# IO_RF.net
KiCad netlist of a schematic drawn in Altium Designer
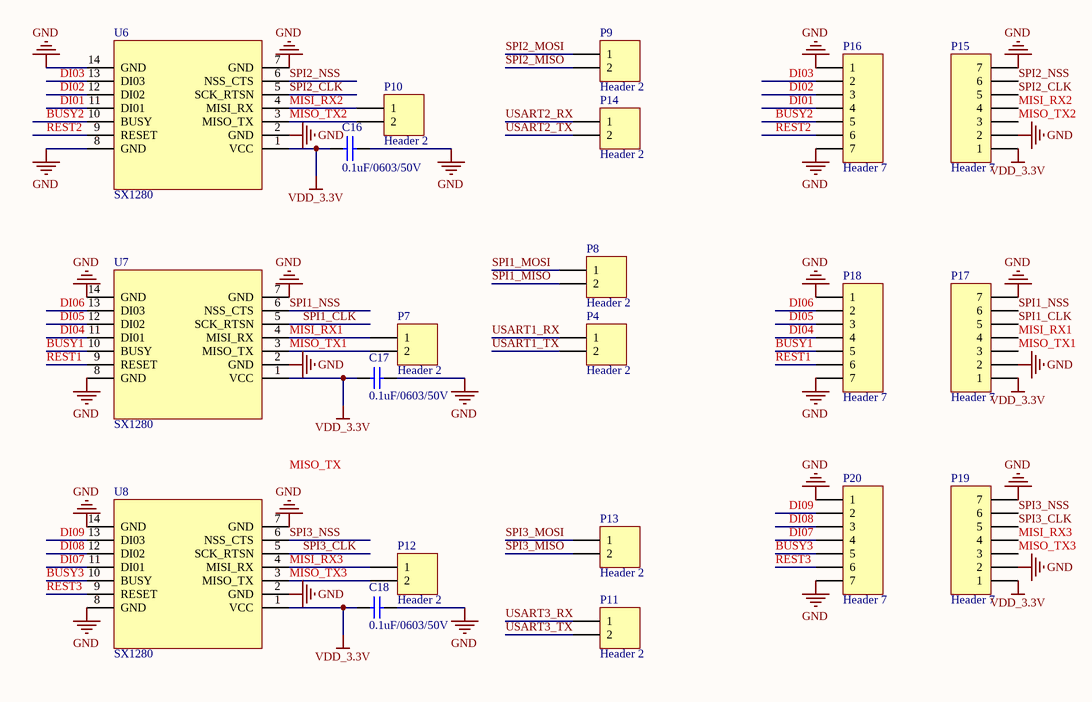
[diagram p0: IO&RF.SchDoc]

(export (version "E")
  (design (tool "Eeschema 10.0.6"))
  (components
    (comp (ref "C16")
      (value "0.1uF/0603/50V")
      (footprint "0603")
      (description "Capacitor")
      (libsource (lib "*") (part "CAP"))
    )
    (comp (ref "C17")
      (value "0.1uF/0603/50V")
      (footprint "0603")
      (description "Capacitor")
      (fields (field (name "PUBLISHER") "Altium Limited"))
      (libsource (lib "Miscellaneous Devices") (part "Cap"))
    )
    (comp (ref "C18")
      (value "0.1uF/0603/50V")
      (footprint "0603")
      (description "Capacitor")
      (fields (field (name "PUBLISHER") "Altium Limited"))
      (libsource (lib "Miscellaneous Devices") (part "Cap"))
    )
    (comp (ref "P4")
      (value "Header 2")
      (footprint "HDR1X2")
      (description "Header, 2-Pin")
      (fields (field (name "PUBLISHER") "Altium Limited"))
      (libsource (lib "Miscellaneous Connectors") (part "Header 2"))
    )
    (comp (ref "P7")
      (value "Header 2")
      (footprint "HDR1X2")
      (description "Header, 2-Pin")
      (fields (field (name "PUBLISHER") "Altium Limited"))
      (libsource (lib "Miscellaneous Connectors") (part "Header 2"))
    )
    (comp (ref "P8")
      (value "Header 2")
      (footprint "HDR1X2")
      (description "Header, 2-Pin")
      (fields (field (name "PUBLISHER") "Altium Limited"))
      (libsource (lib "Miscellaneous Connectors") (part "Header 2"))
    )
    (comp (ref "P9")
      (value "Header 2")
      (footprint "HDR1X2")
      (description "Header, 2-Pin")
      (fields (field (name "PUBLISHER") "Altium Limited"))
      (libsource (lib "Miscellaneous Connectors") (part "Header 2"))
    )
    (comp (ref "P10")
      (value "Header 2")
      (footprint "HDR1X2")
      (description "Header, 2-Pin")
      (fields (field (name "PUBLISHER") "Altium Limited"))
      (libsource (lib "Miscellaneous Connectors") (part "Header 2"))
    )
    (comp (ref "P11")
      (value "Header 2")
      (footprint "HDR1X2")
      (description "Header, 2-Pin")
      (fields (field (name "PUBLISHER") "Altium Limited"))
      (libsource (lib "Miscellaneous Connectors") (part "Header 2"))
    )
    (comp (ref "P12")
      (value "Header 2")
      (footprint "HDR1X2")
      (description "Header, 2-Pin")
      (fields (field (name "PUBLISHER") "Altium Limited"))
      (libsource (lib "Miscellaneous Connectors") (part "Header 2"))
    )
    (comp (ref "P13")
      (value "Header 2")
      (footprint "HDR1X2")
      (description "Header, 2-Pin")
      (fields (field (name "PUBLISHER") "Altium Limited"))
      (libsource (lib "Miscellaneous Connectors") (part "Header 2"))
    )
    (comp (ref "P14")
      (value "Header 2")
      (footprint "HDR1X2")
      (description "Header, 2-Pin")
      (fields (field (name "PUBLISHER") "Altium Limited"))
      (libsource (lib "Miscellaneous Connectors") (part "Header 2"))
    )
    (comp (ref "P15")
      (value "Header 7")
      (footprint "HDR1X7")
      (description "Header, 7-Pin")
      (fields (field (name "PUBLISHER") "Altium Limited"))
      (libsource (lib "PD100") (part "Header 7"))
    )
    (comp (ref "P16")
      (value "Header 7")
      (footprint "HDR1X7")
      (description "Header, 7-Pin")
      (fields (field (name "PUBLISHER") "Altium Limited"))
      (libsource (lib "") (part "Header 7_1"))
    )
    (comp (ref "P17")
      (value "Header 7")
      (footprint "HDR1X7")
      (description "Header, 7-Pin")
      (fields (field (name "PUBLISHER") "Altium Limited"))
      (libsource (lib "PD100") (part "Header 7"))
    )
    (comp (ref "P18")
      (value "Header 7")
      (footprint "HDR1X7")
      (description "Header, 7-Pin")
      (fields (field (name "PUBLISHER") "Altium Limited"))
      (libsource (lib "") (part "Header 7_1"))
    )
    (comp (ref "P19")
      (value "Header 7")
      (footprint "HDR1X7")
      (description "Header, 7-Pin")
      (fields (field (name "PUBLISHER") "Altium Limited"))
      (libsource (lib "PD100") (part "Header 7"))
    )
    (comp (ref "P20")
      (value "Header 7")
      (footprint "HDR1X7")
      (description "Header, 7-Pin")
      (fields (field (name "PUBLISHER") "Altium Limited"))
      (libsource (lib "") (part "Header 7_1"))
    )
    (comp (ref "U6") (value "SX1280") (footprint "PE28(2G4M12S)") (libsource (lib "PD100") (part "SX1280")))
    (comp (ref "U7") (value "SX1280") (footprint "PE28(2G4M12S)") (libsource (lib "PD100") (part "SX1280")))
    (comp (ref "U8") (value "SX1280") (footprint "PE28(2G4M12S)") (libsource (lib "PD100") (part "SX1280")))
  )
  (nets
    (net (code "1") (name "/BUSY1") (class "Default")
      (node (ref "P18") (pin "5") (pinfunction "5_5") (pintype "passive"))
      (node (ref "U7") (pin "10") (pinfunction "BUSY_10") (pintype "passive"))
    )
    (net (code "2") (name "/BUSY2") (class "Default")
      (node (ref "P16") (pin "5") (pinfunction "5_5") (pintype "passive"))
      (node (ref "U6") (pin "10") (pinfunction "BUSY_10") (pintype "passive"))
    )
    (net (code "3") (name "/BUSY3") (class "Default")
      (node (ref "P20") (pin "5") (pinfunction "5_5") (pintype "passive"))
      (node (ref "U8") (pin "10") (pinfunction "BUSY_10") (pintype "passive"))
    )
    (net (code "4") (name "/DI01") (class "Default")
      (node (ref "P16") (pin "4") (pinfunction "4_4") (pintype "passive"))
      (node (ref "U6") (pin "11") (pinfunction "DI01_11") (pintype "passive"))
    )
    (net (code "5") (name "/DI02") (class "Default")
      (node (ref "P16") (pin "3") (pinfunction "3_3") (pintype "passive"))
      (node (ref "U6") (pin "12") (pinfunction "DI02_12") (pintype "passive"))
    )
    (net (code "6") (name "/DI03") (class "Default")
      (node (ref "P16") (pin "2") (pinfunction "2_2") (pintype "passive"))
      (node (ref "U6") (pin "13") (pinfunction "DI03_13") (pintype "passive"))
    )
    (net (code "7") (name "/DI04") (class "Default")
      (node (ref "P18") (pin "4") (pinfunction "4_4") (pintype "passive"))
      (node (ref "U7") (pin "11") (pinfunction "DI01_11") (pintype "passive"))
    )
    (net (code "8") (name "/DI05") (class "Default")
      (node (ref "P18") (pin "3") (pinfunction "3_3") (pintype "passive"))
      (node (ref "U7") (pin "12") (pinfunction "DI02_12") (pintype "passive"))
    )
    (net (code "9") (name "/DI06") (class "Default")
      (node (ref "P18") (pin "2") (pinfunction "2_2") (pintype "passive"))
      (node (ref "U7") (pin "13") (pinfunction "DI03_13") (pintype "passive"))
    )
    (net (code "10") (name "/DI07") (class "Default")
      (node (ref "P20") (pin "4") (pinfunction "4_4") (pintype "passive"))
      (node (ref "U8") (pin "11") (pinfunction "DI01_11") (pintype "passive"))
    )
    (net (code "11") (name "/DI08") (class "Default")
      (node (ref "P20") (pin "3") (pinfunction "3_3") (pintype "passive"))
      (node (ref "U8") (pin "12") (pinfunction "DI02_12") (pintype "passive"))
    )
    (net (code "12") (name "/DI09") (class "Default")
      (node (ref "P20") (pin "2") (pinfunction "2_2") (pintype "passive"))
      (node (ref "U8") (pin "13") (pinfunction "DI03_13") (pintype "passive"))
    )
    (net (code "13") (name "/MISI_RX1") (class "Default")
      (node (ref "P17") (pin "4") (pinfunction "4_4") (pintype "passive"))
      (node (ref "P7") (pin "1") (pinfunction "1_1") (pintype "passive"))
      (node (ref "U7") (pin "4") (pinfunction "MISI_RX_4") (pintype "passive"))
    )
    (net (code "14") (name "/MISI_RX2") (class "Default")
      (node (ref "P10") (pin "1") (pinfunction "1_1") (pintype "passive"))
      (node (ref "P15") (pin "4") (pinfunction "4_4") (pintype "passive"))
      (node (ref "U6") (pin "4") (pinfunction "MISI_RX_4") (pintype "passive"))
    )
    (net (code "15") (name "/MISI_RX3") (class "Default")
      (node (ref "P12") (pin "1") (pinfunction "1_1") (pintype "passive"))
      (node (ref "P19") (pin "4") (pinfunction "4_4") (pintype "passive"))
      (node (ref "U8") (pin "4") (pinfunction "MISI_RX_4") (pintype "passive"))
    )
    (net (code "17") (name "/MISO_TX1") (class "Default")
      (node (ref "P17") (pin "3") (pinfunction "3_3") (pintype "passive"))
      (node (ref "P7") (pin "2") (pinfunction "2_2") (pintype "passive"))
      (node (ref "U7") (pin "3") (pinfunction "MISO_TX_3") (pintype "passive"))
    )
    (net (code "18") (name "/MISO_TX2") (class "Default")
      (node (ref "P10") (pin "2") (pinfunction "2_2") (pintype "passive"))
      (node (ref "P15") (pin "3") (pinfunction "3_3") (pintype "passive"))
      (node (ref "U6") (pin "3") (pinfunction "MISO_TX_3") (pintype "passive"))
    )
    (net (code "19") (name "/MISO_TX3") (class "Default")
      (node (ref "P12") (pin "2") (pinfunction "2_2") (pintype "passive"))
      (node (ref "P19") (pin "3") (pinfunction "3_3") (pintype "passive"))
      (node (ref "U8") (pin "3") (pinfunction "MISO_TX_3") (pintype "passive"))
    )
    (net (code "20") (name "/REST1") (class "Default")
      (node (ref "P18") (pin "6") (pinfunction "6_6") (pintype "passive"))
      (node (ref "U7") (pin "9") (pinfunction "RESET_9") (pintype "passive"))
    )
    (net (code "21") (name "/REST2") (class "Default")
      (node (ref "P16") (pin "6") (pinfunction "6_6") (pintype "passive"))
      (node (ref "U6") (pin "9") (pinfunction "RESET_9") (pintype "passive"))
    )
    (net (code "22") (name "/REST3") (class "Default")
      (node (ref "P20") (pin "6") (pinfunction "6_6") (pintype "passive"))
      (node (ref "U8") (pin "9") (pinfunction "RESET_9") (pintype "passive"))
    )
    (net (code "23") (name "/SPI1_CLK") (class "Default")
      (node (ref "P17") (pin "5") (pinfunction "5_5") (pintype "passive"))
      (node (ref "U7") (pin "5") (pinfunction "SCK_RTSN_5") (pintype "passive"))
    )
    (net (code "24") (name "/SPI1_MISO") (class "Default")
      (node (ref "P8") (pin "2") (pinfunction "2_2") (pintype "passive"))
    )
    (net (code "25") (name "/SPI1_MOSI") (class "Default")
      (node (ref "P8") (pin "1") (pinfunction "1_1") (pintype "passive"))
    )
    (net (code "26") (name "/SPI1_NSS") (class "Default")
      (node (ref "P17") (pin "6") (pinfunction "6_6") (pintype "passive"))
      (node (ref "U7") (pin "6") (pinfunction "NSS_CTS_6") (pintype "passive"))
    )
    (net (code "27") (name "/SPI2_CLK") (class "Default")
      (node (ref "P15") (pin "5") (pinfunction "5_5") (pintype "passive"))
      (node (ref "U6") (pin "5") (pinfunction "SCK_RTSN_5") (pintype "passive"))
    )
    (net (code "28") (name "/SPI2_MISO") (class "Default")
      (node (ref "P9") (pin "2") (pinfunction "2_2") (pintype "passive"))
    )
    (net (code "29") (name "/SPI2_MOSI") (class "Default")
      (node (ref "P9") (pin "1") (pinfunction "1_1") (pintype "passive"))
    )
    (net (code "30") (name "/SPI2_NSS") (class "Default")
      (node (ref "P15") (pin "6") (pinfunction "6_6") (pintype "passive"))
      (node (ref "U6") (pin "6") (pinfunction "NSS_CTS_6") (pintype "passive"))
    )
    (net (code "31") (name "/SPI3_CLK") (class "Default")
      (node (ref "P19") (pin "5") (pinfunction "5_5") (pintype "passive"))
      (node (ref "U8") (pin "5") (pinfunction "SCK_RTSN_5") (pintype "passive"))
    )
    (net (code "32") (name "/SPI3_MISO") (class "Default")
      (node (ref "P13") (pin "2") (pinfunction "2_2") (pintype "passive"))
    )
    (net (code "33") (name "/SPI3_MOSI") (class "Default")
      (node (ref "P13") (pin "1") (pinfunction "1_1") (pintype "passive"))
    )
    (net (code "34") (name "/SPI3_NSS") (class "Default")
      (node (ref "P19") (pin "6") (pinfunction "6_6") (pintype "passive"))
      (node (ref "U8") (pin "6") (pinfunction "NSS_CTS_6") (pintype "passive"))
    )
    (net (code "35") (name "/USART1_RX") (class "Default")
      (node (ref "P4") (pin "1") (pinfunction "1_1") (pintype "passive"))
    )
    (net (code "36") (name "/USART1_TX") (class "Default")
      (node (ref "P4") (pin "2") (pinfunction "2_2") (pintype "passive"))
    )
    (net (code "37") (name "/USART2_RX") (class "Default")
      (node (ref "P14") (pin "1") (pinfunction "1_1") (pintype "passive"))
    )
    (net (code "38") (name "/USART2_TX") (class "Default")
      (node (ref "P14") (pin "2") (pinfunction "2_2") (pintype "passive"))
    )
    (net (code "39") (name "/USART3_RX") (class "Default")
      (node (ref "P11") (pin "1") (pinfunction "1_1") (pintype "passive"))
    )
    (net (code "40") (name "/USART3_TX") (class "Default")
      (node (ref "P11") (pin "2") (pinfunction "2_2") (pintype "passive"))
    )
    (net (code "41") (name "GND") (class "Default")
      (node (ref "C16") (pin "1") (pinfunction "1_1") (pintype "passive"))
      (node (ref "C17") (pin "2") (pinfunction "2_2") (pintype "passive"))
      (node (ref "C18") (pin "2") (pinfunction "2_2") (pintype "passive"))
      (node (ref "P15") (pin "2") (pinfunction "2_2") (pintype "passive"))
      (node (ref "P15") (pin "7") (pinfunction "7_7") (pintype "passive"))
      (node (ref "P16") (pin "1") (pinfunction "1_1") (pintype "passive"))
      (node (ref "P16") (pin "7") (pinfunction "7_7") (pintype "passive"))
      (node (ref "P17") (pin "2") (pinfunction "2_2") (pintype "passive"))
      (node (ref "P17") (pin "7") (pinfunction "7_7") (pintype "passive"))
      (node (ref "P18") (pin "1") (pinfunction "1_1") (pintype "passive"))
      (node (ref "P18") (pin "7") (pinfunction "7_7") (pintype "passive"))
      (node (ref "P19") (pin "2") (pinfunction "2_2") (pintype "passive"))
      (node (ref "P19") (pin "7") (pinfunction "7_7") (pintype "passive"))
      (node (ref "P20") (pin "1") (pinfunction "1_1") (pintype "passive"))
      (node (ref "P20") (pin "7") (pinfunction "7_7") (pintype "passive"))
      (node (ref "U6") (pin "14") (pinfunction "GND_14") (pintype "passive"))
      (node (ref "U6") (pin "2") (pinfunction "GND_2") (pintype "passive"))
      (node (ref "U6") (pin "7") (pinfunction "GND_7") (pintype "passive"))
      (node (ref "U6") (pin "8") (pinfunction "GND_8") (pintype "passive"))
      (node (ref "U7") (pin "14") (pinfunction "GND_14") (pintype "passive"))
      (node (ref "U7") (pin "2") (pinfunction "GND_2") (pintype "passive"))
      (node (ref "U7") (pin "7") (pinfunction "GND_7") (pintype "passive"))
      (node (ref "U7") (pin "8") (pinfunction "GND_8") (pintype "passive"))
      (node (ref "U8") (pin "14") (pinfunction "GND_14") (pintype "passive"))
      (node (ref "U8") (pin "2") (pinfunction "GND_2") (pintype "passive"))
      (node (ref "U8") (pin "7") (pinfunction "GND_7") (pintype "passive"))
      (node (ref "U8") (pin "8") (pinfunction "GND_8") (pintype "passive"))
    )
    (net (code "42") (name "VDD_3.3V") (class "Default")
      (node (ref "C16") (pin "2") (pinfunction "2_2") (pintype "passive"))
      (node (ref "C17") (pin "1") (pinfunction "1_1") (pintype "passive"))
      (node (ref "C18") (pin "1") (pinfunction "1_1") (pintype "passive"))
      (node (ref "P15") (pin "1") (pinfunction "1_1") (pintype "passive"))
      (node (ref "P17") (pin "1") (pinfunction "1_1") (pintype "passive"))
      (node (ref "P19") (pin "1") (pinfunction "1_1") (pintype "passive"))
      (node (ref "U6") (pin "1") (pinfunction "VCC_1") (pintype "passive"))
      (node (ref "U7") (pin "1") (pinfunction "VCC_1") (pintype "passive"))
      (node (ref "U8") (pin "1") (pinfunction "VCC_1") (pintype "passive"))
    )
  )
)
